# ADC-ADC.net
KiCad netlist of a schematic drawn in Altium Designer
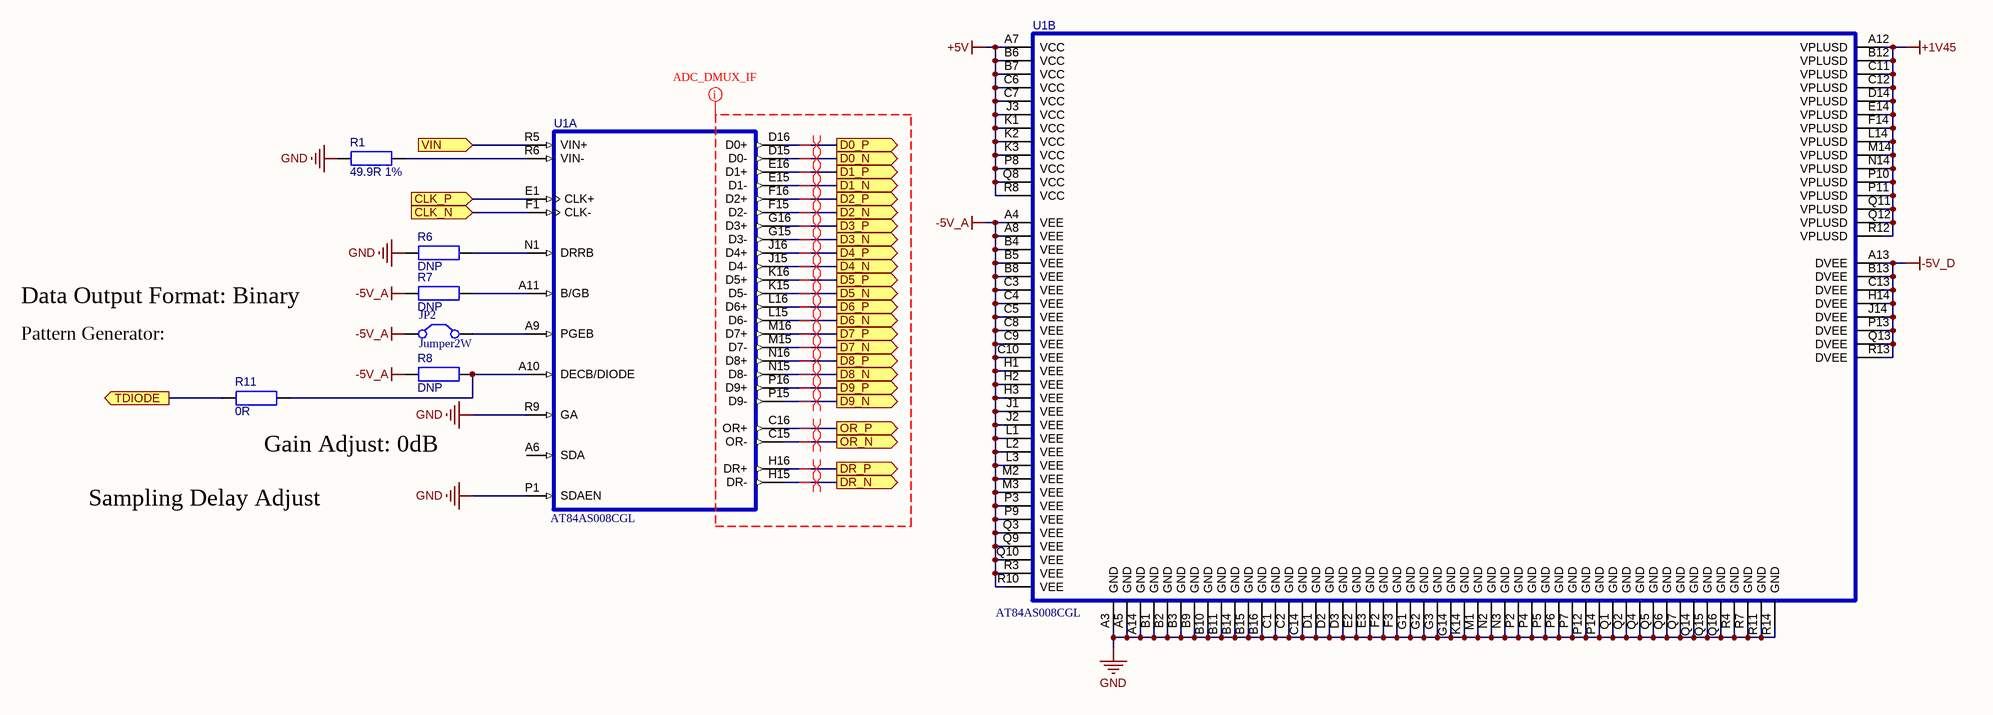
[diagram p0: ADC-ADC.SchDoc]

(export (version "E")
  (design (tool "Eeschema 10.0.6"))
  (components
    (comp (ref "JP2")
      (value "Jumper2W")
      (footprint "JP-100MIL")
      (description "Jumper Wire")
      (fields (field (name "PUBLISHER") "Altium Limited"))
      (libsource (lib "ADC1X2200-10_V1-0") (part "Jumper2W"))
    )
    (comp (ref "R1")
      (value "49.9R 1%")
      (footprint "0603")
      (description "RESISTOR SMD 0805")
      (fields (field (name "CREATED_BY") "*") (field (name "CHECKED_BY") "NN"))
      (libsource (lib "EDA_Passive") (part "RES-0805"))
    )
    (comp (ref "R6")
      (value "DNP")
      (footprint "0603")
      (description "RESISTOR SMD 0603")
      (fields (field (name "CREATED_BY") "*") (field (name "CHECKED_BY") "NN"))
      (libsource (lib "EDA_Passive") (part "RES-0805"))
    )
    (comp (ref "R7")
      (value "DNP")
      (footprint "0603")
      (description "RESISTOR SMD 0603")
      (fields (field (name "CREATED_BY") "*") (field (name "CHECKED_BY") "NN"))
      (libsource (lib "EDA_Passive") (part "RES-0805"))
    )
    (comp (ref "R8")
      (value "DNP")
      (footprint "0603")
      (description "RESISTOR SMD 0603")
      (fields (field (name "CREATED_BY") "*") (field (name "CHECKED_BY") "NN"))
      (libsource (lib "EDA_Passive") (part "RES-0805"))
    )
    (comp (ref "R11")
      (value "0R")
      (footprint "0603")
      (description "RESISTOR SMD 0603")
      (fields (field (name "CREATED_BY") "*") (field (name "CHECKED_BY") "NN"))
      (libsource (lib "EDA_Passive") (part "RES-0805"))
    )
    (comp (ref "U1")
      (value "AT84AS008CGL")
      (footprint "BGA156x16")
      (description "10-bit 2.2Gsps ADC")
      (fields
        (field (name "MANUFACTURER") "e2V")
        (field (name "CREATED_BY") "IN")
        (field (name "CHECKED_BY") "*")
      )
      (libsource (lib "ADC1X2200-10_V1-1") (part "AT84AS008CGL"))
    )
  )
  (nets
    (net (code "1") (name "+1V45") (class "Default")
      (node (ref "U1") (pin "A12") (pinfunction "VPLUSD_A12") (pintype "power_in"))
      (node (ref "U1") (pin "B12") (pinfunction "VPLUSD_B12") (pintype "power_in"))
      (node (ref "U1") (pin "C11") (pinfunction "VPLUSD_C11") (pintype "power_in"))
      (node (ref "U1") (pin "C12") (pinfunction "VPLUSD_C12") (pintype "power_in"))
      (node (ref "U1") (pin "D14") (pinfunction "VPLUSD_D14") (pintype "power_in"))
      (node (ref "U1") (pin "E14") (pinfunction "VPLUSD_E14") (pintype "power_in"))
      (node (ref "U1") (pin "F14") (pinfunction "VPLUSD_F14") (pintype "power_in"))
      (node (ref "U1") (pin "L14") (pinfunction "VPLUSD_L14") (pintype "power_in"))
      (node (ref "U1") (pin "M14") (pinfunction "VPLUSD_M14") (pintype "power_in"))
      (node (ref "U1") (pin "N14") (pinfunction "VPLUSD_N14") (pintype "power_in"))
      (node (ref "U1") (pin "P10") (pinfunction "VPLUSD_P10") (pintype "power_in"))
      (node (ref "U1") (pin "P11") (pinfunction "VPLUSD_P11") (pintype "power_in"))
      (node (ref "U1") (pin "Q11") (pinfunction "VPLUSD_Q11") (pintype "power_in"))
      (node (ref "U1") (pin "Q12") (pinfunction "VPLUSD_Q12") (pintype "power_in"))
      (node (ref "U1") (pin "R12") (pinfunction "VPLUSD_R12") (pintype "power_in"))
    )
    (net (code "2") (name "+5V") (class "Default")
      (node (ref "U1") (pin "A7") (pinfunction "VCC_A7") (pintype "power_in"))
      (node (ref "U1") (pin "B6") (pinfunction "VCC_B6") (pintype "power_in"))
      (node (ref "U1") (pin "B7") (pinfunction "VCC_B7") (pintype "power_in"))
      (node (ref "U1") (pin "C6") (pinfunction "VCC_C6") (pintype "power_in"))
      (node (ref "U1") (pin "C7") (pinfunction "VCC_C7") (pintype "power_in"))
      (node (ref "U1") (pin "J3") (pinfunction "VCC_J3") (pintype "power_in"))
      (node (ref "U1") (pin "K1") (pinfunction "VCC_K1") (pintype "power_in"))
      (node (ref "U1") (pin "K2") (pinfunction "VCC_K2") (pintype "power_in"))
      (node (ref "U1") (pin "K3") (pinfunction "VCC_K3") (pintype "power_in"))
      (node (ref "U1") (pin "P8") (pinfunction "VCC_P8") (pintype "power_in"))
      (node (ref "U1") (pin "Q8") (pinfunction "VCC_Q8") (pintype "power_in"))
      (node (ref "U1") (pin "R8") (pinfunction "VCC_R8") (pintype "power_in"))
    )
    (net (code "3") (name "-5V_A") (class "Default")
      (node (ref "JP2") (pin "1") (pinfunction "C1_1") (pintype "passive"))
      (node (ref "R7") (pin "1") (pinfunction "1_1") (pintype "passive"))
      (node (ref "R8") (pin "1") (pinfunction "1_1") (pintype "passive"))
      (node (ref "U1") (pin "A4") (pinfunction "VEE_A4") (pintype "power_in"))
      (node (ref "U1") (pin "A8") (pinfunction "VEE_A8") (pintype "power_in"))
      (node (ref "U1") (pin "B4") (pinfunction "VEE_B4") (pintype "power_in"))
      (node (ref "U1") (pin "B5") (pinfunction "VEE_B5") (pintype "power_in"))
      (node (ref "U1") (pin "B8") (pinfunction "VEE_B8") (pintype "power_in"))
      (node (ref "U1") (pin "C10") (pinfunction "VEE_C10") (pintype "power_in"))
      (node (ref "U1") (pin "C3") (pinfunction "VEE_C3") (pintype "power_in"))
      (node (ref "U1") (pin "C4") (pinfunction "VEE_C4") (pintype "power_in"))
      (node (ref "U1") (pin "C5") (pinfunction "VEE_C5") (pintype "power_in"))
      (node (ref "U1") (pin "C8") (pinfunction "VEE_C8") (pintype "power_in"))
      (node (ref "U1") (pin "C9") (pinfunction "VEE_C9") (pintype "power_in"))
      (node (ref "U1") (pin "H1") (pinfunction "VEE_H1") (pintype "power_in"))
      (node (ref "U1") (pin "H2") (pinfunction "VEE_H2") (pintype "power_in"))
      (node (ref "U1") (pin "H3") (pinfunction "VEE_H3") (pintype "power_in"))
      (node (ref "U1") (pin "J1") (pinfunction "VEE_J1") (pintype "power_in"))
      (node (ref "U1") (pin "J2") (pinfunction "VEE_J2") (pintype "power_in"))
      (node (ref "U1") (pin "L1") (pinfunction "VEE_L1") (pintype "power_in"))
      (node (ref "U1") (pin "L2") (pinfunction "VEE_L2") (pintype "power_in"))
      (node (ref "U1") (pin "L3") (pinfunction "VEE_L3") (pintype "power_in"))
      (node (ref "U1") (pin "M2") (pinfunction "VEE_M2") (pintype "power_in"))
      (node (ref "U1") (pin "M3") (pinfunction "VEE_M3") (pintype "power_in"))
      (node (ref "U1") (pin "P3") (pinfunction "VEE_P3") (pintype "power_in"))
      (node (ref "U1") (pin "P9") (pinfunction "VEE_P9") (pintype "power_in"))
      (node (ref "U1") (pin "Q10") (pinfunction "VEE_Q10") (pintype "power_in"))
      (node (ref "U1") (pin "Q3") (pinfunction "VEE_Q3") (pintype "power_in"))
      (node (ref "U1") (pin "Q9") (pinfunction "VEE_Q9") (pintype "power_in"))
      (node (ref "U1") (pin "R10") (pinfunction "VEE_R10") (pintype "power_in"))
      (node (ref "U1") (pin "R3") (pinfunction "VEE_R3") (pintype "power_in"))
    )
    (net (code "4") (name "-5V_D") (class "Default")
      (node (ref "U1") (pin "A13") (pinfunction "DVEE_A13") (pintype "power_in"))
      (node (ref "U1") (pin "B13") (pinfunction "DVEE_B13") (pintype "power_in"))
      (node (ref "U1") (pin "C13") (pinfunction "DVEE_C13") (pintype "power_in"))
      (node (ref "U1") (pin "H14") (pinfunction "DVEE_H14") (pintype "power_in"))
      (node (ref "U1") (pin "J14") (pinfunction "DVEE_J14") (pintype "power_in"))
      (node (ref "U1") (pin "P13") (pinfunction "DVEE_P13") (pintype "power_in"))
      (node (ref "U1") (pin "Q13") (pinfunction "DVEE_Q13") (pintype "power_in"))
      (node (ref "U1") (pin "R13") (pinfunction "DVEE_R13") (pintype "power_in"))
    )
    (net (code "5") (name "/CLK_N") (class "Default")
      (node (ref "U1") (pin "F1") (pinfunction "CLK-_F1") (pintype "input"))
    )
    (net (code "6") (name "/CLK_P") (class "Default")
      (node (ref "U1") (pin "E1") (pinfunction "CLK+_E1") (pintype "input"))
    )
    (net (code "7") (name "/D0_N") (class "Default")
      (node (ref "U1") (pin "D15") (pinfunction "D0-_D15") (pintype "output"))
    )
    (net (code "8") (name "/D0_P") (class "Default")
      (node (ref "U1") (pin "D16") (pinfunction "D0+_D16") (pintype "output"))
    )
    (net (code "9") (name "/D1_N") (class "Default")
      (node (ref "U1") (pin "E15") (pinfunction "D1-_E15") (pintype "output"))
    )
    (net (code "10") (name "/D1_P") (class "Default")
      (node (ref "U1") (pin "E16") (pinfunction "D1+_E16") (pintype "output"))
    )
    (net (code "11") (name "/D2_N") (class "Default")
      (node (ref "U1") (pin "F15") (pinfunction "D2-_F15") (pintype "output"))
    )
    (net (code "12") (name "/D2_P") (class "Default")
      (node (ref "U1") (pin "F16") (pinfunction "D2+_F16") (pintype "output"))
    )
    (net (code "13") (name "/D3_N") (class "Default")
      (node (ref "U1") (pin "G15") (pinfunction "D3-_G15") (pintype "output"))
    )
    (net (code "14") (name "/D3_P") (class "Default")
      (node (ref "U1") (pin "G16") (pinfunction "D3+_G16") (pintype "output"))
    )
    (net (code "15") (name "/D4_N") (class "Default")
      (node (ref "U1") (pin "J15") (pinfunction "D4-_J15") (pintype "output"))
    )
    (net (code "16") (name "/D4_P") (class "Default")
      (node (ref "U1") (pin "J16") (pinfunction "D4+_J16") (pintype "output"))
    )
    (net (code "17") (name "/D5_N") (class "Default")
      (node (ref "U1") (pin "K15") (pinfunction "D5-_K15") (pintype "output"))
    )
    (net (code "18") (name "/D5_P") (class "Default")
      (node (ref "U1") (pin "K16") (pinfunction "D5+_K16") (pintype "output"))
    )
    (net (code "19") (name "/D6_N") (class "Default")
      (node (ref "U1") (pin "L15") (pinfunction "D6-_L15") (pintype "output"))
    )
    (net (code "20") (name "/D6_P") (class "Default")
      (node (ref "U1") (pin "L16") (pinfunction "D6+_L16") (pintype "output"))
    )
    (net (code "21") (name "/D7_N") (class "Default")
      (node (ref "U1") (pin "M15") (pinfunction "D7-_M15") (pintype "output"))
    )
    (net (code "22") (name "/D7_P") (class "Default")
      (node (ref "U1") (pin "M16") (pinfunction "D7+_M16") (pintype "output"))
    )
    (net (code "23") (name "/D8_N") (class "Default")
      (node (ref "U1") (pin "N15") (pinfunction "D8-_N15") (pintype "output"))
    )
    (net (code "24") (name "/D8_P") (class "Default")
      (node (ref "U1") (pin "N16") (pinfunction "D8+_N16") (pintype "output"))
    )
    (net (code "25") (name "/D9_N") (class "Default")
      (node (ref "U1") (pin "P15") (pinfunction "D9-_P15") (pintype "output"))
    )
    (net (code "26") (name "/D9_P") (class "Default")
      (node (ref "U1") (pin "P16") (pinfunction "D9+_P16") (pintype "output"))
    )
    (net (code "27") (name "/DR_N") (class "Default")
      (node (ref "U1") (pin "H15") (pinfunction "DR-_H15") (pintype "output"))
    )
    (net (code "28") (name "/DR_P") (class "Default")
      (node (ref "U1") (pin "H16") (pinfunction "DR+_H16") (pintype "output"))
    )
    (net (code "29") (name "/OR_N") (class "Default")
      (node (ref "U1") (pin "C15") (pinfunction "OR-_C15") (pintype "output"))
    )
    (net (code "30") (name "/OR_P") (class "Default")
      (node (ref "U1") (pin "C16") (pinfunction "OR+_C16") (pintype "output"))
    )
    (net (code "31") (name "/TDIODE") (class "Default")
      (node (ref "R11") (pin "1") (pinfunction "1_1") (pintype "passive"))
    )
    (net (code "32") (name "/VIN") (class "Default")
      (node (ref "U1") (pin "R5") (pinfunction "VIN+_R5") (pintype "input"))
    )
    (net (code "33") (name "GND") (class "Default")
      (node (ref "R1") (pin "1") (pinfunction "1_1") (pintype "passive"))
      (node (ref "R6") (pin "1") (pinfunction "1_1") (pintype "passive"))
      (node (ref "U1") (pin "A14") (pinfunction "GND_A14") (pintype "power_in"))
      (node (ref "U1") (pin "A3") (pinfunction "GND_A3") (pintype "power_in"))
      (node (ref "U1") (pin "A5") (pinfunction "GND_A5") (pintype "power_in"))
      (node (ref "U1") (pin "B1") (pinfunction "GND_B1") (pintype "power_in"))
      (node (ref "U1") (pin "B10") (pinfunction "GND_B10") (pintype "power_in"))
      (node (ref "U1") (pin "B11") (pinfunction "GND_B11") (pintype "power_in"))
      (node (ref "U1") (pin "B14") (pinfunction "GND_B14") (pintype "power_in"))
      (node (ref "U1") (pin "B15") (pinfunction "GND_B15") (pintype "power_in"))
      (node (ref "U1") (pin "B16") (pinfunction "GND_B16") (pintype "power_in"))
      (node (ref "U1") (pin "B2") (pinfunction "GND_B2") (pintype "power_in"))
      (node (ref "U1") (pin "B3") (pinfunction "GND_B3") (pintype "power_in"))
      (node (ref "U1") (pin "B9") (pinfunction "GND_B9") (pintype "power_in"))
      (node (ref "U1") (pin "C1") (pinfunction "GND_C1") (pintype "power_in"))
      (node (ref "U1") (pin "C14") (pinfunction "GND_C14") (pintype "power_in"))
      (node (ref "U1") (pin "C2") (pinfunction "GND_C2") (pintype "power_in"))
      (node (ref "U1") (pin "D1") (pinfunction "GND_D1") (pintype "power_in"))
      (node (ref "U1") (pin "D2") (pinfunction "GND_D2") (pintype "power_in"))
      (node (ref "U1") (pin "D3") (pinfunction "GND_D3") (pintype "power_in"))
      (node (ref "U1") (pin "E2") (pinfunction "GND_E2") (pintype "power_in"))
      (node (ref "U1") (pin "E3") (pinfunction "GND_E3") (pintype "power_in"))
      (node (ref "U1") (pin "F2") (pinfunction "GND_F2") (pintype "power_in"))
      (node (ref "U1") (pin "F3") (pinfunction "GND_F3") (pintype "power_in"))
      (node (ref "U1") (pin "G1") (pinfunction "GND_G1") (pintype "power_in"))
      (node (ref "U1") (pin "G14") (pinfunction "GND_G14") (pintype "power_in"))
      (node (ref "U1") (pin "G2") (pinfunction "GND_G2") (pintype "power_in"))
      (node (ref "U1") (pin "G3") (pinfunction "GND_G3") (pintype "power_in"))
      (node (ref "U1") (pin "K14") (pinfunction "GND_K14") (pintype "power_in"))
      (node (ref "U1") (pin "M1") (pinfunction "GND_M1") (pintype "power_in"))
      (node (ref "U1") (pin "N2") (pinfunction "GND_N2") (pintype "power_in"))
      (node (ref "U1") (pin "N3") (pinfunction "GND_N3") (pintype "power_in"))
      (node (ref "U1") (pin "P1") (pinfunction "SDAEN_P1") (pintype "input"))
      (node (ref "U1") (pin "P12") (pinfunction "GND_P12") (pintype "power_in"))
      (node (ref "U1") (pin "P14") (pinfunction "GND_P14") (pintype "power_in"))
      (node (ref "U1") (pin "P2") (pinfunction "GND_P2") (pintype "power_in"))
      (node (ref "U1") (pin "P4") (pinfunction "GND_P4") (pintype "power_in"))
      (node (ref "U1") (pin "P5") (pinfunction "GND_P5") (pintype "power_in"))
      (node (ref "U1") (pin "P6") (pinfunction "GND_P6") (pintype "power_in"))
      (node (ref "U1") (pin "P7") (pinfunction "GND_P7") (pintype "power_in"))
      (node (ref "U1") (pin "Q1") (pinfunction "GND_Q1") (pintype "power_in"))
      (node (ref "U1") (pin "Q14") (pinfunction "GND_Q14") (pintype "power_in"))
      (node (ref "U1") (pin "Q15") (pinfunction "GND_Q15") (pintype "power_in"))
      (node (ref "U1") (pin "Q16") (pinfunction "GND_Q16") (pintype "power_in"))
      (node (ref "U1") (pin "Q2") (pinfunction "GND_Q2") (pintype "power_in"))
      (node (ref "U1") (pin "Q4") (pinfunction "GND_Q4") (pintype "power_in"))
      (node (ref "U1") (pin "Q5") (pinfunction "GND_Q5") (pintype "power_in"))
      (node (ref "U1") (pin "Q6") (pinfunction "GND_Q6") (pintype "power_in"))
      (node (ref "U1") (pin "Q7") (pinfunction "GND_Q7") (pintype "power_in"))
      (node (ref "U1") (pin "R11") (pinfunction "GND_R11") (pintype "power_in"))
      (node (ref "U1") (pin "R14") (pinfunction "GND_R14") (pintype "power_in"))
      (node (ref "U1") (pin "R4") (pinfunction "GND_R4") (pintype "power_in"))
      (node (ref "U1") (pin "R7") (pinfunction "GND_R7") (pintype "power_in"))
      (node (ref "U1") (pin "R9") (pinfunction "GA_R9") (pintype "input"))
    )
    (net (code "34") (name "Net-(JP2-C2)") (class "Default")
      (node (ref "JP2") (pin "2") (pinfunction "C2_2") (pintype "passive"))
      (node (ref "U1") (pin "A9") (pinfunction "PGEB_A9") (pintype "input"))
    )
    (net (code "35") (name "Net-(U1A-B{slash}GB)") (class "Default")
      (node (ref "R7") (pin "2") (pinfunction "2_2") (pintype "passive"))
      (node (ref "U1") (pin "A11") (pinfunction "B/GB_A11") (pintype "input"))
    )
    (net (code "36") (name "Net-(U1A-DECB{slash}DIODE)") (class "Default")
      (node (ref "R11") (pin "2") (pinfunction "2_2") (pintype "passive"))
      (node (ref "R8") (pin "2") (pinfunction "2_2") (pintype "passive"))
      (node (ref "U1") (pin "A10") (pinfunction "DECB/DIODE_A10") (pintype "input"))
    )
    (net (code "37") (name "Net-(U1A-DRRB)") (class "Default")
      (node (ref "R6") (pin "2") (pinfunction "2_2") (pintype "passive"))
      (node (ref "U1") (pin "N1") (pinfunction "DRRB_N1") (pintype "input"))
    )
    (net (code "38") (name "Net-(U1A-VIN-)") (class "Default")
      (node (ref "R1") (pin "2") (pinfunction "2_2") (pintype "passive"))
      (node (ref "U1") (pin "R6") (pinfunction "VIN-_R6") (pintype "input"))
    )
    (net (code "39") (name "unconnected-(U1A-SDA-PadA6)") (class "Default")
      (node (ref "U1") (pin "A6") (pinfunction "SDA_A6") (pintype "input"))
    )
  )
)
